# MC3_microcontroller.net
KiCad netlist of a schematic drawn in Altium Designer
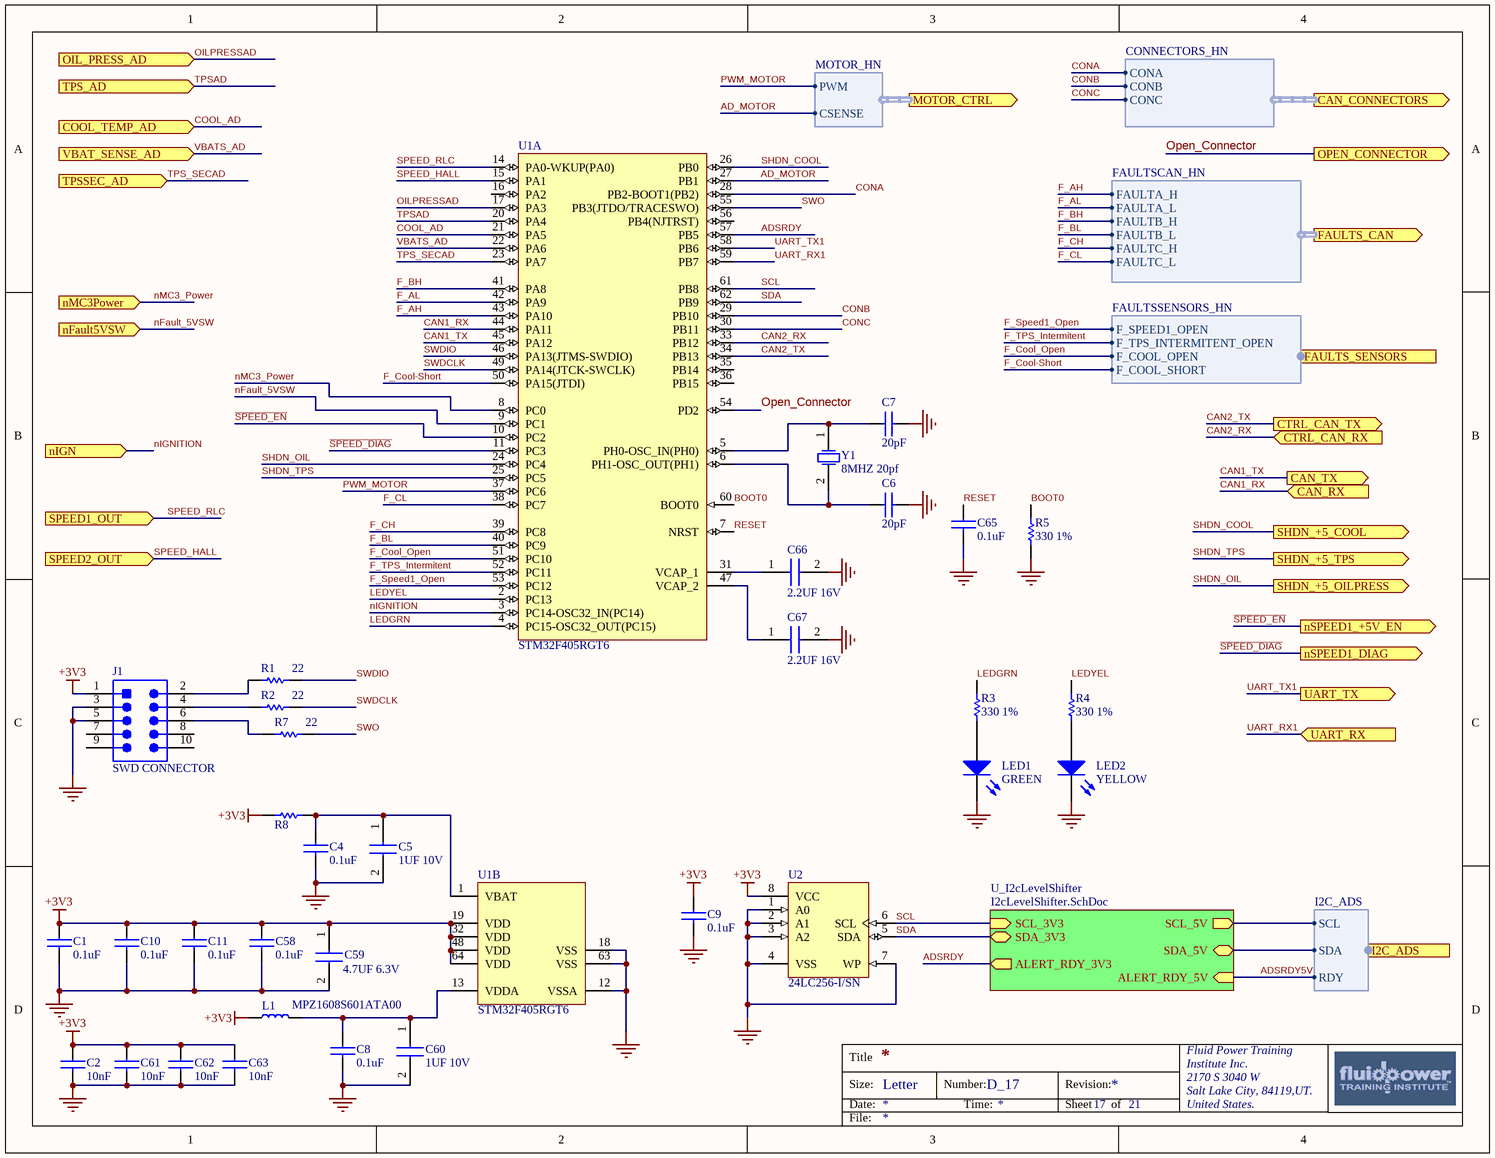
[diagram p0: MC3_microcontroller.SchDoc]

(export (version "E")
  (design (tool "Eeschema 10.0.6"))
  (components
    (comp (ref "C1")
      (value "0.1uF")
      (footprint "C0805")
      (description "Cap Ceramic 0.1uF 50V X7R 10% SMD 2.0 x 1.2 mm 125 C Paper T/R")
      (fields
        (field (name "MANUFACTURER") "KEMET")
        (field (name "MANUFACTURER PART NUMBER") "C0805C104K5RACTU")
      )
      (libsource (lib "MCx") (part "C0805C104K5RACTU"))
    )
    (comp (ref "C2")
      (value "10nF")
      (footprint "C0805")
      (fields
        (field (name "MANUFACTURER") "Yageo")
        (field (name "MANUFACTURER PART NUMBER") "CC0805KRX7R9BB103")
        (field (name "TOLERANCE") "10%")
      )
      (libsource (lib "MCx") (part "CC0805KRX7R9BB103"))
    )
    (comp (ref "C4")
      (value "0.1uF")
      (footprint "C0805")
      (description "Cap Ceramic 0.1uF 50V X7R 10% SMD 2.0 x 1.2 mm 125 C Paper T/R")
      (fields
        (field (name "MANUFACTURER") "KEMET")
        (field (name "MANUFACTURER PART NUMBER") "C0805C104K5RACTU")
      )
      (libsource (lib "MCx") (part "C0805C104K5RACTU"))
    )
    (comp (ref "C5")
      (value "1UF 10V")
      (footprint "MC1:CAPC1608X90X20LL10")
      (description "Cap Ceramic 1uF 10V X5R 10% SMD 0603 85°C Paper T/R")
      (fields
        (field (name "MANUFACTURER") "KEMET")
        (field (name "MANUFACTURER PART NUMBER") "C0603C105K8PACTU")
      )
      (libsource (lib "MC1") (part "C0603C105K8PACTU"))
    )
    (comp (ref "C6")
      (value "20pF")
      (footprint "C0805")
      (description "AVX - 08051A200JAT2A - CERAMIC CAPACITOR 20PF 100V, C0G, 5%, 0805, FULL REEL")
      (fields
        (field (name "MANUFACTURER") "Kyocera AVX")
        (field (name "MANUFACTURER PART NUMBER") "08051A200JAT2A")
      )
      (libsource (lib "MCx") (part "08051A200JAT2A"))
    )
    (comp (ref "C7")
      (value "20pF")
      (footprint "C0805")
      (description "AVX - 08051A200JAT2A - CERAMIC CAPACITOR 20PF 100V, C0G, 5%, 0805, FULL REEL")
      (fields
        (field (name "MANUFACTURER") "Kyocera AVX")
        (field (name "MANUFACTURER PART NUMBER") "08051A200JAT2A")
      )
      (libsource (lib "MCx") (part "08051A200JAT2A"))
    )
    (comp (ref "C8")
      (value "0.1uF")
      (footprint "C0805")
      (description "Cap Ceramic 0.1uF 50V X7R 10% SMD 2.0 x 1.2 mm 125 C Paper T/R")
      (fields
        (field (name "MANUFACTURER") "KEMET")
        (field (name "MANUFACTURER PART NUMBER") "C0805C104K5RACTU")
      )
      (libsource (lib "MCx") (part "C0805C104K5RACTU"))
    )
    (comp (ref "C9")
      (value "0.1uF")
      (footprint "C0805")
      (description "Cap Ceramic 0.1uF 50V X7R 10% SMD 2.0 x 1.2 mm 125 C Paper T/R")
      (fields
        (field (name "MANUFACTURER") "KEMET")
        (field (name "MANUFACTURER PART NUMBER") "C0805C104K5RACTU")
      )
      (libsource (lib "MCx") (part "C0805C104K5RACTU"))
    )
    (comp (ref "C10")
      (value "0.1uF")
      (footprint "C0805")
      (description "Cap Ceramic 0.1uF 50V X7R 10% SMD 2.0 x 1.2 mm 125 C Paper T/R")
      (fields
        (field (name "MANUFACTURER") "KEMET")
        (field (name "MANUFACTURER PART NUMBER") "C0805C104K5RACTU")
      )
      (libsource (lib "MCx") (part "C0805C104K5RACTU"))
    )
    (comp (ref "C11")
      (value "0.1uF")
      (footprint "C0805")
      (description "Cap Ceramic 0.1uF 50V X7R 10% SMD 2.0 x 1.2 mm 125 C Paper T/R")
      (fields
        (field (name "MANUFACTURER") "KEMET")
        (field (name "MANUFACTURER PART NUMBER") "C0805C104K5RACTU")
      )
      (libsource (lib "MCx") (part "C0805C104K5RACTU"))
    )
    (comp (ref "C58")
      (value "0.1uF")
      (footprint "C0805")
      (description "Cap Ceramic 0.1uF 50V X7R 10% SMD 2.0 x 1.2 mm 125 C Paper T/R")
      (fields
        (field (name "MANUFACTURER") "KEMET")
        (field (name "MANUFACTURER PART NUMBER") "C0805C104K5RACTU")
      )
      (libsource (lib "MCx") (part "C0805C104K5RACTU"))
    )
    (comp (ref "C59")
      (value "4.7UF 6.3V")
      (footprint "MC1:CAPC1608X90X20LL10")
      (description "KEMET - C0603C475K9PACTU - KONDENSATOR, 4.7µF, 6.3V, 10%, X5R, 0603")
      (fields
        (field (name "MANUFACTURER") "KEMET")
        (field (name "MANUFACTURER PART NUMBER") "C0603C475K9PACTU")
      )
      (libsource (lib "MC1") (part "C0603C475K9PACTU"))
    )
    (comp (ref "C60")
      (value "1UF 10V")
      (footprint "MC1:CAPC1608X90X20LL10")
      (description "Cap Ceramic 1uF 10V X5R 10% SMD 0603 85°C Paper T/R")
      (fields
        (field (name "MANUFACTURER") "KEMET")
        (field (name "MANUFACTURER PART NUMBER") "C0603C105K8PACTU")
      )
      (libsource (lib "MC1") (part "C0603C105K8PACTU"))
    )
    (comp (ref "C61")
      (value "10nF")
      (footprint "C0805")
      (fields
        (field (name "MANUFACTURER") "Yageo")
        (field (name "MANUFACTURER PART NUMBER") "CC0805KRX7R9BB103")
        (field (name "TOLERANCE") "10%")
      )
      (libsource (lib "MCx") (part "CC0805KRX7R9BB103"))
    )
    (comp (ref "C62")
      (value "10nF")
      (footprint "C0805")
      (fields
        (field (name "MANUFACTURER") "Yageo")
        (field (name "MANUFACTURER PART NUMBER") "CC0805KRX7R9BB103")
        (field (name "TOLERANCE") "10%")
      )
      (libsource (lib "MCx") (part "CC0805KRX7R9BB103"))
    )
    (comp (ref "C63")
      (value "10nF")
      (footprint "C0805")
      (fields
        (field (name "MANUFACTURER") "Yageo")
        (field (name "MANUFACTURER PART NUMBER") "CC0805KRX7R9BB103")
        (field (name "TOLERANCE") "10%")
      )
      (libsource (lib "MCx") (part "CC0805KRX7R9BB103"))
    )
    (comp (ref "C65")
      (value "0.1uF")
      (footprint "C0805")
      (description "Cap Ceramic 0.1uF 50V X7R 10% SMD 2.0 x 1.2 mm 125 C Paper T/R")
      (fields
        (field (name "MANUFACTURER") "KEMET")
        (field (name "MANUFACTURER PART NUMBER") "C0805C104K5RACTU")
      )
      (libsource (lib "MCx") (part "C0805C104K5RACTU"))
    )
    (comp (ref "C66")
      (value "2.2UF 16V")
      (footprint "MC1:CAPC1608X09M")
      (description "KEMET - C0603C225K4PACTU - CAP, MLCC, X5R, 2.2UF, 16V, 0603")
      (fields
        (field (name "MANUFACTURER") "KEMET")
        (field (name "MANUFACTURER PART NUMBER") "C0603C225K4PACTU")
      )
      (libsource (lib "MC1") (part "C0603C225K4PACTU"))
    )
    (comp (ref "C67")
      (value "2.2UF 16V")
      (footprint "MC1:CAPC1608X09M")
      (description "KEMET - C0603C225K4PACTU - CAP, MLCC, X5R, 2.2UF, 16V, 0603")
      (fields
        (field (name "MANUFACTURER") "KEMET")
        (field (name "MANUFACTURER PART NUMBER") "C0603C225K4PACTU")
      )
      (libsource (lib "MC1") (part "C0603C225K4PACTU"))
    )
    (comp (ref "J1")
      (value "SWD CONNECTOR")
      (footprint "MC1:SMTC-FTSH-105-01-L-DV-K_V")
      (description "SAMTEC - FTSH-105-01-F-DV-K - HEADER, 1.27 MM, SURFACE MOUNT, 10 CONTACTS")
      (fields
        (field (name "MANUFACTURER") "Samtec")
        (field (name "MANUFACTURER PART NUMBER") "FTSH-105-01-F-DV-K")
      )
      (libsource (lib "MC1") (part "FTSH-105-01-F-DV-K"))
    )
    (comp (ref "L1")
      (value "MPZ1608S601ATA00")
      (footprint "MC1:INDC1608X06L")
      (description "TDK         MPZ1608S601ATA00            FERRITE BEAD, 0.15OHM, 1A, 0603, FULL REEL")
      (fields (field (name "MANUFACTURER") "TDK EPCOS") (field (name "TOLERANCE") "25%"))
      (libsource (lib "MC1") (part "MPZ1608S601ATA00"))
    )
    (comp (ref "LED1")
      (value "GREEN")
      (footprint "LED0805")
      (description "LED GREEN CLEAR 0805 SMD")
      (fields
        (field (name "MANUFACTURER") "Wurth Electronics")
        (field (name "MANUFACTURER PART NUMBER") "150080VS75000")
      )
      (libsource (lib "MCx") (part "150080VS75000"))
    )
    (comp (ref "LED2")
      (value "YELLOW")
      (footprint "LED0805")
      (description "LED YELLOW CLEAR 0805 SMD")
      (fields
        (field (name "MANUFACTURER") "Wurth Electronics")
        (field (name "MANUFACTURER PART NUMBER") "150080YS75000")
      )
      (libsource (lib "MCx") (part "150080YS75000"))
    )
    (comp (ref "R1")
      (value "22")
      (footprint "R0805")
      (description "Resistor;  Thick Film;  22 Ohms;  0.125 W;  5%;  SMT;  0805;  TCR 73 ppm/DegC;  Cut Tape")
      (fields
        (field (name "MANUFACTURER") "Vishay Dale")
        (field (name "MANUFACTURER PART NUMBER") "CRCW080522R0JNEA")
      )
      (libsource (lib "MCx") (part "CRCW080522R0JNEA"))
    )
    (comp (ref "R2")
      (value "22")
      (footprint "R0805")
      (description "Resistor;  Thick Film;  22 Ohms;  0.125 W;  5%;  SMT;  0805;  TCR 73 ppm/DegC;  Cut Tape")
      (fields
        (field (name "MANUFACTURER") "Vishay Dale")
        (field (name "MANUFACTURER PART NUMBER") "CRCW080522R0JNEA")
      )
      (libsource (lib "MCx") (part "CRCW080522R0JNEA"))
    )
    (comp (ref "R3")
      (value "330 1%")
      (footprint "R0805")
      (description "RES SMD 330 OHM 1% 1/8W 0805")
      (fields
        (field (name "MANUFACTURER") "Panasonic")
        (field (name "MANUFACTURER PART NUMBER") "ERJ-6ENF3300V")
      )
      (libsource (lib "MCx") (part "ERJ-6ENF3300V"))
    )
    (comp (ref "R4")
      (value "330 1%")
      (footprint "R0805")
      (description "RES SMD 330 OHM 1% 1/8W 0805")
      (fields
        (field (name "MANUFACTURER") "Panasonic")
        (field (name "MANUFACTURER PART NUMBER") "ERJ-6ENF3300V")
      )
      (libsource (lib "MCx") (part "ERJ-6ENF3300V"))
    )
    (comp (ref "R5")
      (value "330 1%")
      (footprint "R0805")
      (description "RES SMD 330 OHM 1% 1/8W 0805")
      (fields
        (field (name "MANUFACTURER") "Panasonic")
        (field (name "MANUFACTURER PART NUMBER") "ERJ-6ENF3300V")
      )
      (libsource (lib "MCx") (part "ERJ-6ENF3300V"))
    )
    (comp (ref "R7")
      (value "22")
      (footprint "R0805")
      (description "Resistor;  Thick Film;  22 Ohms;  0.125 W;  5%;  SMT;  0805;  TCR 73 ppm/DegC;  Cut Tape")
      (fields
        (field (name "MANUFACTURER") "Vishay Dale")
        (field (name "MANUFACTURER PART NUMBER") "CRCW080522R0JNEA")
      )
      (libsource (lib "MCx") (part "CRCW080522R0JNEA"))
    )
    (comp (ref "R8")
      (value "0 OHM")
      (footprint "R0805")
      (description "Res Thick Film 0805 0 Ohm Pad SMD Automotive T/R")
      (fields
        (field (name "MANUFACTURER") "KOA Speer")
        (field (name "MANUFACTURER PART NUMBER") "RK73Z2ATTD")
      )
      (libsource (lib "MCx") (part "RK73Z2ATTD"))
    )
    (comp (ref "U1")
      (value "STM32F405RGT6")
      (footprint "MC1:STM-LQFP64_V")
      (fields (field (name "MANUFACTURER") "STMicroelectronics"))
      (libsource (lib "MC1") (part "STM32F405RGT6"))
    )
    (comp (ref "U2")
      (value "24LC256-I/SN")
      (footprint "MC1:SOIC-SN8_L")
      (fields (field (name "MANUFACTURER") "Microchip") (field (name "VOLTAGE") "5V"))
      (libsource (lib "MC1") (part "24LC256-I/SN"))
    )
    (comp (ref "Y1")
      (value "8MHZ 20pf")
      (footprint "MC1:HC49US")
      (description "CRYSTAL 8.0000MHZ 20PF SMD")
      (fields
        (field (name "MANUFACTURER") "ECS International")
        (field (name "MANUFACTURER PART NUMBER") "ECS-80-20-5G3XDS-TR")
      )
      (libsource (lib "MC1") (part "ECS-80-20-5G3XDS-TR"))
    )
  )
  (nets
    (net (code "6") (name "+3V3") (class "Default")
      (node (ref "C1") (pin "1") (pinfunction "1_1") (pintype "passive"))
      (node (ref "C10") (pin "1") (pinfunction "1_1") (pintype "passive"))
      (node (ref "C11") (pin "1") (pinfunction "1_1") (pintype "passive"))
      (node (ref "C2") (pin "1") (pinfunction "1_1") (pintype "passive"))
      (node (ref "C58") (pin "1") (pinfunction "1_1") (pintype "passive"))
      (node (ref "C59") (pin "1") (pinfunction "1_1") (pintype "passive"))
      (node (ref "C61") (pin "1") (pinfunction "1_1") (pintype "passive"))
      (node (ref "C62") (pin "1") (pinfunction "1_1") (pintype "passive"))
      (node (ref "C63") (pin "1") (pinfunction "1_1") (pintype "passive"))
      (node (ref "C9") (pin "1") (pinfunction "1_1") (pintype "passive"))
      (node (ref "J1") (pin "1") (pinfunction "1_1") (pintype "passive"))
      (node (ref "L1") (pin "1") (pinfunction "1_1") (pintype "passive"))
      (node (ref "R8") (pin "1") (pinfunction "1_1") (pintype "passive"))
      (node (ref "U1") (pin "19") (pinfunction "VDD_19") (pintype "power_in"))
      (node (ref "U1") (pin "32") (pinfunction "VDD_32") (pintype "power_in"))
      (node (ref "U1") (pin "48") (pinfunction "VDD_48") (pintype "power_in"))
      (node (ref "U1") (pin "64") (pinfunction "VDD_64") (pintype "power_in"))
      (node (ref "U2") (pin "8") (pinfunction "VCC_8") (pintype "power_in"))
    )
    (net (code "7") (name "/ADSRDY") (class "Default")
      (node (ref "U1") (pin "57") (pinfunction "PB5_57") (pintype "bidirectional"))
    )
    (net (code "9") (name "/AD_MOTOR") (class "Default")
      (node (ref "U1") (pin "27") (pinfunction "PB1_27") (pintype "bidirectional"))
    )
    (net (code "10") (name "/BOOT0") (class "Default")
      (node (ref "R5") (pin "2") (pinfunction "2_2") (pintype "passive"))
      (node (ref "U1") (pin "60") (pinfunction "BOOT0_60") (pintype "input"))
    )
    (net (code "11") (name "/CAN1_RX") (class "Default")
      (node (ref "U1") (pin "44") (pinfunction "PA11_44") (pintype "bidirectional"))
    )
    (net (code "12") (name "/CAN1_TX") (class "Default")
      (node (ref "U1") (pin "45") (pinfunction "PA12_45") (pintype "bidirectional"))
    )
    (net (code "13") (name "/CAN2_RX") (class "Default")
      (node (ref "U1") (pin "33") (pinfunction "PB12_33") (pintype "bidirectional"))
    )
    (net (code "14") (name "/CAN2_TX") (class "Default")
      (node (ref "U1") (pin "34") (pinfunction "PB13_34") (pintype "bidirectional"))
    )
    (net (code "15") (name "/CONA") (class "Default")
      (node (ref "U1") (pin "28") (pinfunction "PB2-BOOT1(PB2)_28") (pintype "bidirectional"))
    )
    (net (code "16") (name "/CONB") (class "Default")
      (node (ref "U1") (pin "29") (pinfunction "PB10_29") (pintype "bidirectional"))
    )
    (net (code "17") (name "/CONC") (class "Default")
      (node (ref "U1") (pin "30") (pinfunction "PB11_30") (pintype "bidirectional"))
    )
    (net (code "18") (name "/COOL_AD") (class "Default")
      (node (ref "U1") (pin "21") (pinfunction "PA5_21") (pintype "bidirectional"))
    )
    (net (code "19") (name "/F_AH") (class "Default")
      (node (ref "U1") (pin "43") (pinfunction "PA10_43") (pintype "bidirectional"))
    )
    (net (code "20") (name "/F_AL") (class "Default")
      (node (ref "U1") (pin "42") (pinfunction "PA9_42") (pintype "bidirectional"))
    )
    (net (code "21") (name "/F_BH") (class "Default")
      (node (ref "U1") (pin "41") (pinfunction "PA8_41") (pintype "bidirectional"))
    )
    (net (code "22") (name "/F_BL") (class "Default")
      (node (ref "U1") (pin "40") (pinfunction "PC9_40") (pintype "bidirectional"))
    )
    (net (code "23") (name "/F_CH") (class "Default")
      (node (ref "U1") (pin "39") (pinfunction "PC8_39") (pintype "bidirectional"))
    )
    (net (code "24") (name "/F_CL") (class "Default")
      (node (ref "U1") (pin "38") (pinfunction "PC7_38") (pintype "bidirectional"))
    )
    (net (code "25") (name "/F_Cool-Short") (class "Default")
      (node (ref "U1") (pin "50") (pinfunction "PA15(JTDI)_50") (pintype "bidirectional"))
    )
    (net (code "26") (name "/F_Cool_Open") (class "Default")
      (node (ref "U1") (pin "51") (pinfunction "PC10_51") (pintype "bidirectional"))
    )
    (net (code "27") (name "/F_Speed1_Open") (class "Default")
      (node (ref "U1") (pin "53") (pinfunction "PC12_53") (pintype "bidirectional"))
    )
    (net (code "28") (name "/F_TPS_Intermitent") (class "Default")
      (node (ref "U1") (pin "52") (pinfunction "PC11_52") (pintype "bidirectional"))
    )
    (net (code "29") (name "/LEDGRN") (class "Default")
      (node (ref "R3") (pin "2") (pinfunction "2_2") (pintype "passive"))
      (node (ref "U1") (pin "4") (pinfunction "PC15-OSC32_OUT(PC15)_4") (pintype "bidirectional"))
    )
    (net (code "30") (name "/LEDYEL") (class "Default")
      (node (ref "R4") (pin "2") (pinfunction "2_2") (pintype "passive"))
      (node (ref "U1") (pin "2") (pinfunction "PC13_2") (pintype "bidirectional"))
    )
    (net (code "31") (name "/OILPRESSAD") (class "Default")
      (node (ref "U1") (pin "17") (pinfunction "PA3_17") (pintype "bidirectional"))
    )
    (net (code "32") (name "/Open_Connector") (class "Default")
      (node (ref "U1") (pin "54") (pinfunction "PD2_54") (pintype "bidirectional"))
    )
    (net (code "33") (name "/PWM_MOTOR") (class "Default")
      (node (ref "U1") (pin "37") (pinfunction "PC6_37") (pintype "bidirectional"))
    )
    (net (code "34") (name "/RESET") (class "Default")
      (node (ref "C65") (pin "1") (pinfunction "1_1") (pintype "passive"))
      (node (ref "U1") (pin "7") (pinfunction "NRST_7") (pintype "bidirectional"))
    )
    (net (code "35") (name "/SCL") (class "Default")
      (node (ref "U1") (pin "61") (pinfunction "PB8_61") (pintype "bidirectional"))
      (node (ref "U2") (pin "6") (pinfunction "SCL_6") (pintype "input"))
    )
    (net (code "37") (name "/SDA") (class "Default")
      (node (ref "U1") (pin "62") (pinfunction "PB9_62") (pintype "bidirectional"))
      (node (ref "U2") (pin "5") (pinfunction "SDA_5") (pintype "bidirectional"))
    )
    (net (code "39") (name "/SHDN_COOL") (class "Default")
      (node (ref "U1") (pin "26") (pinfunction "PB0_26") (pintype "bidirectional"))
    )
    (net (code "40") (name "/SHDN_OIL") (class "Default")
      (node (ref "U1") (pin "24") (pinfunction "PC4_24") (pintype "bidirectional"))
    )
    (net (code "41") (name "/SHDN_TPS") (class "Default")
      (node (ref "U1") (pin "25") (pinfunction "PC5_25") (pintype "bidirectional"))
    )
    (net (code "42") (name "/SPEED_HALL") (class "Default")
      (node (ref "U1") (pin "15") (pinfunction "PA1_15") (pintype "bidirectional"))
    )
    (net (code "43") (name "/SPEED_RLC") (class "Default")
      (node (ref "U1") (pin "14") (pinfunction "PA0-WKUP(PA0)_14") (pintype "bidirectional"))
    )
    (net (code "44") (name "/SWDCLK") (class "Default")
      (node (ref "R2") (pin "2") (pinfunction "2_2") (pintype "passive"))
      (node (ref "U1") (pin "49") (pinfunction "PA14(JTCK-SWCLK)_49") (pintype "bidirectional"))
    )
    (net (code "45") (name "/SWDIO") (class "Default")
      (node (ref "R1") (pin "2") (pinfunction "2_2") (pintype "passive"))
      (node (ref "U1") (pin "46") (pinfunction "PA13(JTMS-SWDIO)_46") (pintype "bidirectional"))
    )
    (net (code "46") (name "/SWO") (class "Default")
      (node (ref "R7") (pin "2") (pinfunction "2_2") (pintype "passive"))
      (node (ref "U1") (pin "55") (pinfunction "PB3(JTDO/TRACESWO)_55") (pintype "bidirectional"))
    )
    (net (code "47") (name "/TPSAD") (class "Default")
      (node (ref "U1") (pin "20") (pinfunction "PA4_20") (pintype "bidirectional"))
    )
    (net (code "48") (name "/TPS_SECAD") (class "Default")
      (node (ref "U1") (pin "23") (pinfunction "PA7_23") (pintype "bidirectional"))
    )
    (net (code "49") (name "/UART_RX1") (class "Default")
      (node (ref "U1") (pin "59") (pinfunction "PB7_59") (pintype "bidirectional"))
    )
    (net (code "50") (name "/UART_TX1") (class "Default")
      (node (ref "U1") (pin "58") (pinfunction "PB6_58") (pintype "bidirectional"))
    )
    (net (code "51") (name "/VBATS_AD") (class "Default")
      (node (ref "U1") (pin "22") (pinfunction "PA6_22") (pintype "bidirectional"))
    )
    (net (code "52") (name "/nFault_5VSW") (class "Default")
      (node (ref "U1") (pin "9") (pinfunction "PC1_9") (pintype "bidirectional"))
    )
    (net (code "53") (name "/nIGNITION") (class "Default")
      (node (ref "U1") (pin "3") (pinfunction "PC14-OSC32_IN(PC14)_3") (pintype "bidirectional"))
    )
    (net (code "54") (name "/nMC3_Power") (class "Default")
      (node (ref "U1") (pin "8") (pinfunction "PC0_8") (pintype "bidirectional"))
    )
    (net (code "60") (name "/~{SPEED_DIAG}") (class "Default")
      (node (ref "U1") (pin "11") (pinfunction "PC3_11") (pintype "bidirectional"))
    )
    (net (code "61") (name "/~{SPEED_EN}") (class "Default")
      (node (ref "U1") (pin "10") (pinfunction "PC2_10") (pintype "bidirectional"))
    )
    (net (code "62") (name "GND") (class "Default")
      (node (ref "C1") (pin "2") (pinfunction "2_2") (pintype "passive"))
      (node (ref "C10") (pin "2") (pinfunction "2_2") (pintype "passive"))
      (node (ref "C11") (pin "2") (pinfunction "2_2") (pintype "passive"))
      (node (ref "C2") (pin "2") (pinfunction "2_2") (pintype "passive"))
      (node (ref "C4") (pin "2") (pinfunction "2_2") (pintype "passive"))
      (node (ref "C5") (pin "2") (pinfunction "2_2") (pintype "passive"))
      (node (ref "C58") (pin "2") (pinfunction "2_2") (pintype "passive"))
      (node (ref "C59") (pin "2") (pinfunction "2_2") (pintype "passive"))
      (node (ref "C6") (pin "2") (pinfunction "2_2") (pintype "passive"))
      (node (ref "C60") (pin "2") (pinfunction "2_2") (pintype "passive"))
      (node (ref "C61") (pin "2") (pinfunction "2_2") (pintype "passive"))
      (node (ref "C62") (pin "2") (pinfunction "2_2") (pintype "passive"))
      (node (ref "C63") (pin "2") (pinfunction "2_2") (pintype "passive"))
      (node (ref "C65") (pin "2") (pinfunction "2_2") (pintype "passive"))
      (node (ref "C66") (pin "2") (pinfunction "2_2") (pintype "passive"))
      (node (ref "C67") (pin "2") (pinfunction "2_2") (pintype "passive"))
      (node (ref "C7") (pin "2") (pinfunction "2_2") (pintype "passive"))
      (node (ref "C8") (pin "2") (pinfunction "2_2") (pintype "passive"))
      (node (ref "C9") (pin "2") (pinfunction "2_2") (pintype "passive"))
      (node (ref "J1") (pin "3") (pinfunction "3_3") (pintype "passive"))
      (node (ref "J1") (pin "5") (pinfunction "5_5") (pintype "passive"))
      (node (ref "LED1") (pin "1") (pinfunction "K_1") (pintype "passive"))
      (node (ref "LED2") (pin "1") (pinfunction "K_1") (pintype "passive"))
      (node (ref "R5") (pin "1") (pinfunction "1_1") (pintype "passive"))
      (node (ref "U1") (pin "12") (pinfunction "VSSA_12") (pintype "power_in"))
      (node (ref "U1") (pin "18") (pinfunction "VSS_18") (pintype "power_in"))
      (node (ref "U1") (pin "63") (pinfunction "VSS_63") (pintype "power_in"))
      (node (ref "U2") (pin "1") (pinfunction "A0_1") (pintype "input"))
      (node (ref "U2") (pin "2") (pinfunction "A1_2") (pintype "input"))
      (node (ref "U2") (pin "3") (pinfunction "A2_3") (pintype "input"))
      (node (ref "U2") (pin "4") (pinfunction "VSS_4") (pintype "power_in"))
      (node (ref "U2") (pin "7") (pinfunction "WP_7") (pintype "input"))
    )
    (net (code "63") (name "Net-(J1-Pad2)") (class "Default")
      (node (ref "J1") (pin "2") (pinfunction "2_2") (pintype "passive"))
      (node (ref "R1") (pin "1") (pinfunction "1_1") (pintype "passive"))
    )
    (net (code "64") (name "Net-(J1-Pad4)") (class "Default")
      (node (ref "J1") (pin "4") (pinfunction "4_4") (pintype "passive"))
      (node (ref "R2") (pin "1") (pinfunction "1_1") (pintype "passive"))
    )
    (net (code "65") (name "Net-(J1-Pad6)") (class "Default")
      (node (ref "J1") (pin "6") (pinfunction "6_6") (pintype "passive"))
      (node (ref "R7") (pin "1") (pinfunction "1_1") (pintype "passive"))
    )
    (net (code "66") (name "Net-(LED1-A)") (class "Default")
      (node (ref "LED1") (pin "2") (pinfunction "A_2") (pintype "passive"))
      (node (ref "R3") (pin "1") (pinfunction "1_1") (pintype "passive"))
    )
    (net (code "67") (name "Net-(LED2-A)") (class "Default")
      (node (ref "LED2") (pin "2") (pinfunction "A_2") (pintype "passive"))
      (node (ref "R4") (pin "1") (pinfunction "1_1") (pintype "passive"))
    )
    (net (code "68") (name "Net-(U1A-PH0-OSC_IN(PH0))") (class "Default")
      (node (ref "C7") (pin "1") (pinfunction "1_1") (pintype "passive"))
      (node (ref "U1") (pin "5") (pinfunction "PH0-OSC_IN(PH0)_5") (pintype "bidirectional"))
      (node (ref "Y1") (pin "1") (pinfunction "1_1") (pintype "passive"))
    )
    (net (code "69") (name "Net-(U1A-PH1-OSC_OUT(PH1))") (class "Default")
      (node (ref "C6") (pin "1") (pinfunction "1_1") (pintype "passive"))
      (node (ref "U1") (pin "6") (pinfunction "PH1-OSC_OUT(PH1)_6") (pintype "bidirectional"))
      (node (ref "Y1") (pin "2") (pinfunction "2_2") (pintype "passive"))
    )
    (net (code "70") (name "Net-(U1A-VCAP_1)") (class "Default")
      (node (ref "C66") (pin "1") (pinfunction "1_1") (pintype "passive"))
      (node (ref "U1") (pin "31") (pinfunction "VCAP_1_31") (pintype "power_in"))
    )
    (net (code "71") (name "Net-(U1A-VCAP_2)") (class "Default")
      (node (ref "C67") (pin "1") (pinfunction "1_1") (pintype "passive"))
      (node (ref "U1") (pin "47") (pinfunction "VCAP_2_47") (pintype "power_in"))
    )
    (net (code "72") (name "Net-(U1B-VBAT)") (class "Default")
      (node (ref "C4") (pin "1") (pinfunction "1_1") (pintype "passive"))
      (node (ref "C5") (pin "1") (pinfunction "1_1") (pintype "passive"))
      (node (ref "R8") (pin "2") (pinfunction "2_2") (pintype "passive"))
      (node (ref "U1") (pin "1") (pinfunction "VBAT_1") (pintype "power_in"))
    )
    (net (code "73") (name "Net-(U1B-VDDA)") (class "Default")
      (node (ref "C60") (pin "1") (pinfunction "1_1") (pintype "passive"))
      (node (ref "C8") (pin "1") (pinfunction "1_1") (pintype "passive"))
      (node (ref "L1") (pin "2") (pinfunction "2_2") (pintype "passive"))
      (node (ref "U1") (pin "13") (pinfunction "VDDA_13") (pintype "power_in"))
    )
    (net (code "74") (name "unconnected-(J1-Pad7)") (class "Default")
      (node (ref "J1") (pin "7") (pinfunction "7_7") (pintype "passive"))
    )
    (net (code "75") (name "unconnected-(J1-Pad8)") (class "Default")
      (node (ref "J1") (pin "8") (pinfunction "8_8") (pintype "passive"))
    )
    (net (code "76") (name "unconnected-(J1-Pad9)") (class "Default")
      (node (ref "J1") (pin "9") (pinfunction "9_9") (pintype "passive"))
    )
    (net (code "77") (name "unconnected-(J1-Pad10)") (class "Default")
      (node (ref "J1") (pin "10") (pinfunction "10_10") (pintype "passive"))
    )
    (net (code "78") (name "unconnected-(U1A-PA2-Pad16)") (class "Default")
      (node (ref "U1") (pin "16") (pinfunction "PA2_16") (pintype "bidirectional"))
    )
    (net (code "79") (name "unconnected-(U1A-PB4(NJTRST)-Pad56)") (class "Default")
      (node (ref "U1") (pin "56") (pinfunction "PB4(NJTRST)_56") (pintype "bidirectional"))
    )
    (net (code "80") (name "unconnected-(U1A-PB14-Pad35)") (class "Default")
      (node (ref "U1") (pin "35") (pinfunction "PB14_35") (pintype "bidirectional"))
    )
    (net (code "81") (name "unconnected-(U1A-PB15-Pad36)") (class "Default")
      (node (ref "U1") (pin "36") (pinfunction "PB15_36") (pintype "bidirectional"))
    )
  )
)
